# Relay.net
KiCad netlist of a schematic drawn in Altium Designer
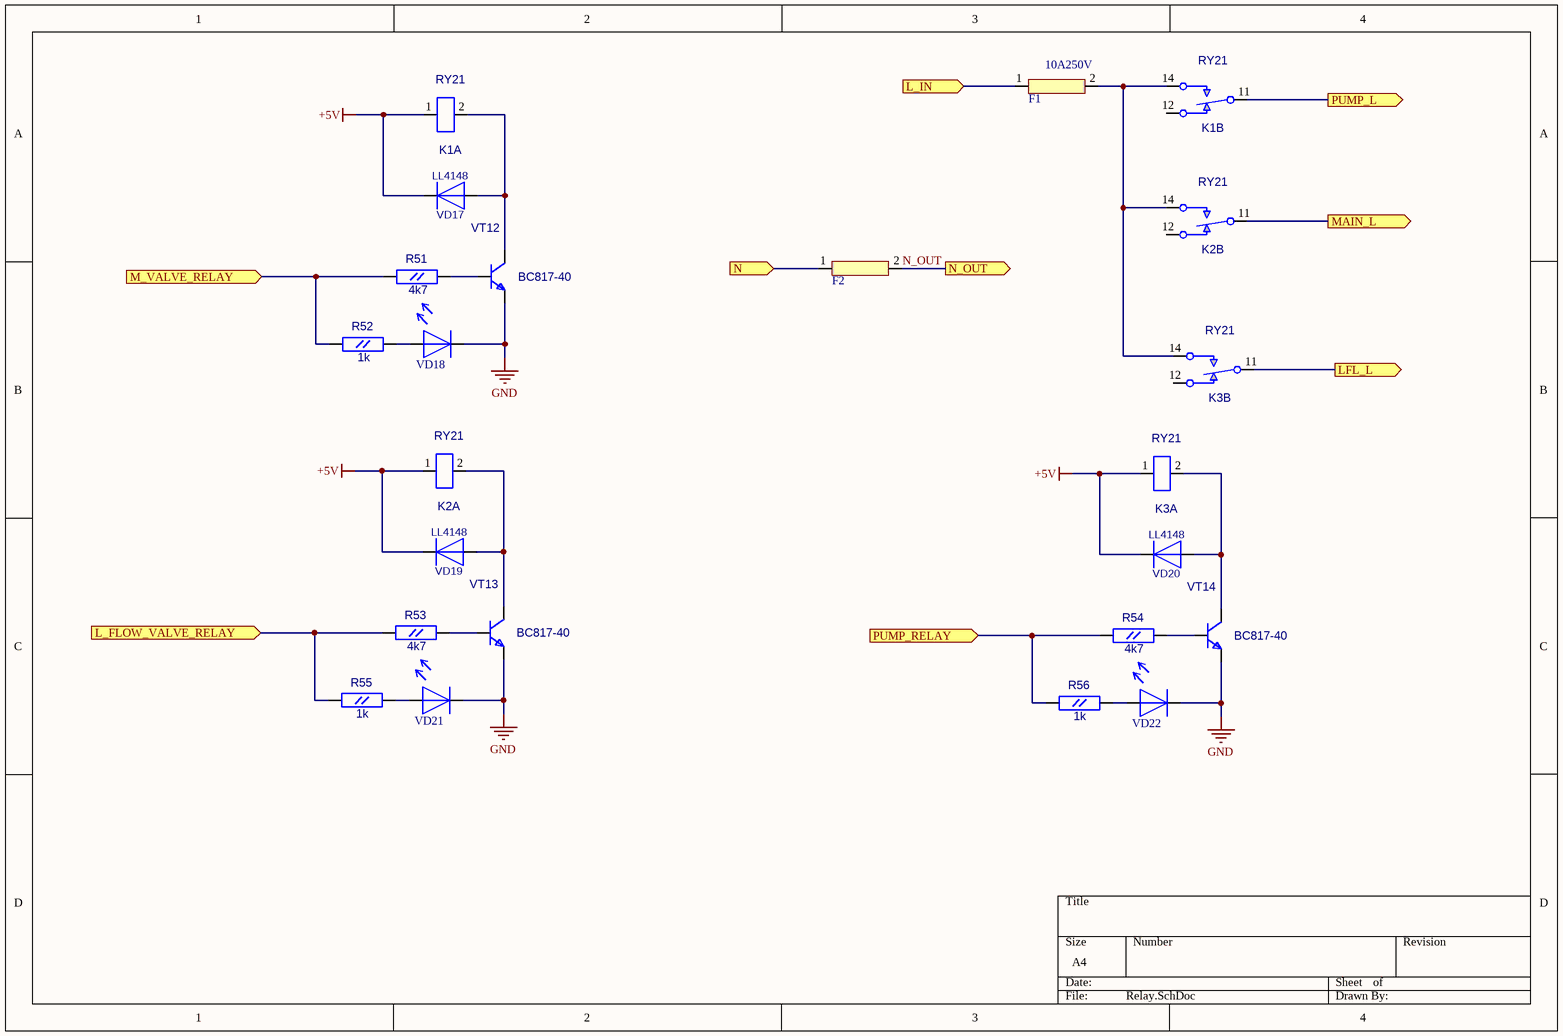
[diagram p0: Relay.SchDoc]

(export (version "E")
  (design (tool "Eeschema 10.0.6"))
  (components
    (comp (ref "F1")
      (value "KLS5-266(5x20) 2pcs")
      (footprint "Fuse_5x20")
      (libsource (lib "gprs_modem_2") (part "Fuse KLS5-266(5x20)"))
    )
    (comp (ref "F2")
      (value "KLS5-266(5x20) 2pcs")
      (footprint "Fuse_5x20")
      (libsource (lib "gprs_modem_2") (part "Fuse KLS5-266(5x20)"))
    )
    (comp (ref "K1")
      (value "RY21")
      (footprint "RY21_RY21(Primary)")
      (libsource (lib "shlagbaum") (part "RY21"))
    )
    (comp (ref "K2") (value "RY21") (footprint "RY21_RY21(Primary)") (libsource (lib "") (part "RY21_1")))
    (comp (ref "K3") (value "RY21") (footprint "RY21_RY21(Primary)") (libsource (lib "") (part "RY21_1")))
    (comp (ref "R51")
      (value "4k7")
      (footprint "RC0603")
      (description "RC0603")
      (libsource (lib "gprs_modem_2") (part "RC0603"))
    )
    (comp (ref "R52")
      (value "1k")
      (footprint "RC0603")
      (description "RC0603")
      (libsource (lib "gprs_modem_2") (part "RC0603"))
    )
    (comp (ref "R53")
      (value "4k7")
      (footprint "RC0603")
      (description "RC0603")
      (libsource (lib "gprs_modem_2") (part "RC0603"))
    )
    (comp (ref "R54")
      (value "4k7")
      (footprint "RC0603")
      (description "RC0603")
      (libsource (lib "gprs_modem_2") (part "RC0603"))
    )
    (comp (ref "R55")
      (value "1k")
      (footprint "RC0603")
      (description "RC0603")
      (libsource (lib "gprs_modem_2") (part "RC0603"))
    )
    (comp (ref "R56")
      (value "1k")
      (footprint "RC0603")
      (description "RC0603")
      (libsource (lib "gprs_modem_2") (part "RC0603"))
    )
    (comp (ref "VD17") (value "LL4148") (footprint "SOD-80") (libsource (lib "gprs_modem_2") (part "LL4148")))
    (comp (ref "VD18")
      (value "LED_0805")
      (footprint "LED0805")
      (libsource (lib "gprs_modem_2") (part "LED_0805"))
    )
    (comp (ref "VD19") (value "LL4148") (footprint "SOD-80") (libsource (lib "gprs_modem_2") (part "LL4148")))
    (comp (ref "VD20") (value "LL4148") (footprint "SOD-80") (libsource (lib "gprs_modem_2") (part "LL4148")))
    (comp (ref "VD21")
      (value "LED_0805")
      (footprint "LED0805")
      (libsource (lib "gprs_modem_2") (part "LED_0805"))
    )
    (comp (ref "VD22")
      (value "LED_0805")
      (footprint "LED0805")
      (libsource (lib "gprs_modem_2") (part "LED_0805"))
    )
    (comp (ref "VT12")
      (value "BC817-40")
      (footprint "SOT-23(123)")
      (description "NPN 500ma transistor")
      (libsource (lib "gprs_modem_2") (part "BC846BLT1"))
    )
    (comp (ref "VT13")
      (value "BC817-40")
      (footprint "SOT-23(123)")
      (description "NPN 500ma transistor")
      (libsource (lib "gprs_modem_2") (part "BC846BLT1"))
    )
    (comp (ref "VT14")
      (value "BC817-40")
      (footprint "SOT-23(123)")
      (description "NPN 500ma transistor")
      (libsource (lib "gprs_modem_2") (part "BC846BLT1"))
    )
  )
  (nets
    (net (code "1") (name "+5V") (class "Default")
      (node (ref "K1") (pin "1") (pinfunction "L1_1") (pintype "passive"))
      (node (ref "K2") (pin "1") (pinfunction "L1_1") (pintype "passive"))
      (node (ref "K3") (pin "1") (pinfunction "L1_1") (pintype "passive"))
      (node (ref "VD17") (pin "2") (pinfunction "+_2") (pintype "passive"))
      (node (ref "VD19") (pin "2") (pinfunction "+_2") (pintype "passive"))
      (node (ref "VD20") (pin "2") (pinfunction "+_2") (pintype "passive"))
    )
    (net (code "2") (name "/LFL_L") (class "Default")
      (node (ref "K3") (pin "11") (pinfunction "C1_11") (pintype "passive"))
    )
    (net (code "3") (name "/L_FLOW_VALVE_RELAY") (class "Default")
      (node (ref "R53") (pin "1") (pinfunction "A_1") (pintype "passive"))
      (node (ref "R55") (pin "1") (pinfunction "A_1") (pintype "passive"))
    )
    (net (code "4") (name "/L_IN") (class "Default")
      (node (ref "F1") (pin "1") (pinfunction "9_1") (pintype "passive"))
    )
    (net (code "5") (name "/MAIN_L") (class "Default")
      (node (ref "K2") (pin "11") (pinfunction "C1_11") (pintype "passive"))
    )
    (net (code "6") (name "/M_VALVE_RELAY") (class "Default")
      (node (ref "R51") (pin "1") (pinfunction "A_1") (pintype "passive"))
      (node (ref "R52") (pin "1") (pinfunction "A_1") (pintype "passive"))
    )
    (net (code "7") (name "/N") (class "Default")
      (node (ref "F2") (pin "1") (pinfunction "9_1") (pintype "passive"))
    )
    (net (code "8") (name "/N_OUT") (class "Default")
      (node (ref "F2") (pin "2") (pinfunction "2_2") (pintype "passive"))
    )
    (net (code "9") (name "/PUMP_L") (class "Default")
      (node (ref "K1") (pin "11") (pinfunction "C1_11") (pintype "passive"))
    )
    (net (code "10") (name "/PUMP_RELAY") (class "Default")
      (node (ref "R54") (pin "1") (pinfunction "A_1") (pintype "passive"))
      (node (ref "R56") (pin "1") (pinfunction "A_1") (pintype "passive"))
    )
    (net (code "11") (name "GND") (class "Default")
      (node (ref "VD18") (pin "2") (pintype "passive"))
      (node (ref "VD21") (pin "2") (pintype "passive"))
      (node (ref "VD22") (pin "2") (pintype "passive"))
      (node (ref "VT12") (pin "2") (pinfunction "E_2") (pintype "passive"))
      (node (ref "VT13") (pin "2") (pinfunction "E_2") (pintype "passive"))
      (node (ref "VT14") (pin "2") (pinfunction "E_2") (pintype "passive"))
    )
    (net (code "12") (name "Net-(K1A-C2)") (class "Default")
      (node (ref "K1") (pin "2") (pinfunction "C2_2") (pintype "passive"))
      (node (ref "VD17") (pin "1") (pinfunction "-_1") (pintype "passive"))
      (node (ref "VT12") (pin "3") (pinfunction "C_3") (pintype "passive"))
    )
    (net (code "13") (name "Net-(K1B-C2)") (class "Default")
      (node (ref "F1") (pin "2") (pinfunction "2_2") (pintype "passive"))
      (node (ref "K1") (pin "14") (pinfunction "C2_14") (pintype "passive"))
      (node (ref "K2") (pin "14") (pinfunction "C2_14") (pintype "passive"))
      (node (ref "K3") (pin "14") (pinfunction "C2_14") (pintype "passive"))
    )
    (net (code "14") (name "Net-(K2A-C2)") (class "Default")
      (node (ref "K2") (pin "2") (pinfunction "C2_2") (pintype "passive"))
      (node (ref "VD19") (pin "1") (pinfunction "-_1") (pintype "passive"))
      (node (ref "VT13") (pin "3") (pinfunction "C_3") (pintype "passive"))
    )
    (net (code "15") (name "Net-(K3A-C2)") (class "Default")
      (node (ref "K3") (pin "2") (pinfunction "C2_2") (pintype "passive"))
      (node (ref "VD20") (pin "1") (pinfunction "-_1") (pintype "passive"))
      (node (ref "VT14") (pin "3") (pinfunction "C_3") (pintype "passive"))
    )
    (net (code "16") (name "Net-(R51-B)") (class "Default")
      (node (ref "R51") (pin "2") (pinfunction "B_2") (pintype "passive"))
      (node (ref "VT12") (pin "1") (pinfunction "B_1") (pintype "passive"))
    )
    (net (code "17") (name "Net-(R52-B)") (class "Default")
      (node (ref "R52") (pin "2") (pinfunction "B_2") (pintype "passive"))
      (node (ref "VD18") (pin "1") (pintype "passive"))
    )
    (net (code "18") (name "Net-(R53-B)") (class "Default")
      (node (ref "R53") (pin "2") (pinfunction "B_2") (pintype "passive"))
      (node (ref "VT13") (pin "1") (pinfunction "B_1") (pintype "passive"))
    )
    (net (code "19") (name "Net-(R54-B)") (class "Default")
      (node (ref "R54") (pin "2") (pinfunction "B_2") (pintype "passive"))
      (node (ref "VT14") (pin "1") (pinfunction "B_1") (pintype "passive"))
    )
    (net (code "20") (name "Net-(R55-B)") (class "Default")
      (node (ref "R55") (pin "2") (pinfunction "B_2") (pintype "passive"))
      (node (ref "VD21") (pin "1") (pintype "passive"))
    )
    (net (code "21") (name "Net-(R56-B)") (class "Default")
      (node (ref "R56") (pin "2") (pinfunction "B_2") (pintype "passive"))
      (node (ref "VD22") (pin "1") (pintype "passive"))
    )
    (net (code "22") (name "unconnected-(K1B-C3-Pad12)") (class "Default")
      (node (ref "K1") (pin "12") (pinfunction "C3_12") (pintype "passive"))
    )
    (net (code "23") (name "unconnected-(K2B-C3-Pad12)") (class "Default")
      (node (ref "K2") (pin "12") (pinfunction "C3_12") (pintype "passive"))
    )
    (net (code "24") (name "unconnected-(K3B-C3-Pad12)") (class "Default")
      (node (ref "K3") (pin "12") (pinfunction "C3_12") (pintype "passive"))
    )
  )
)
